# Schematic.net
KiCad netlist of a schematic drawn in Altium Designer
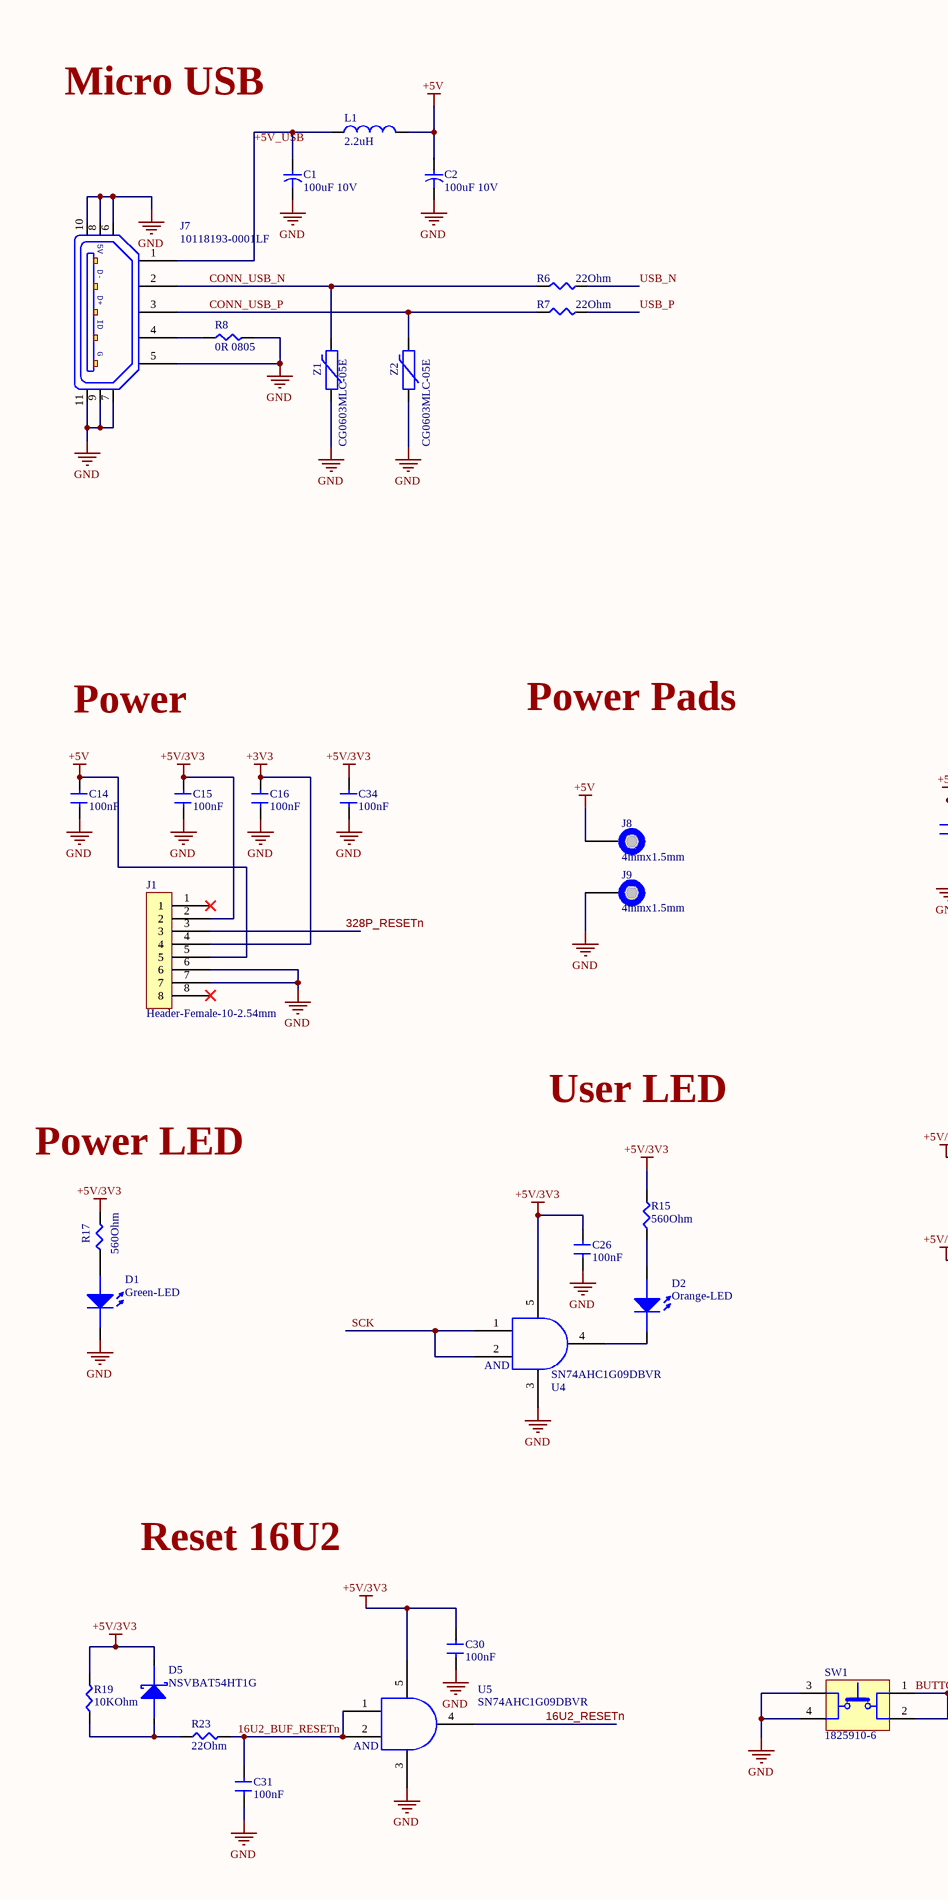
[diagram p0: Schematic.SchDoc, left]
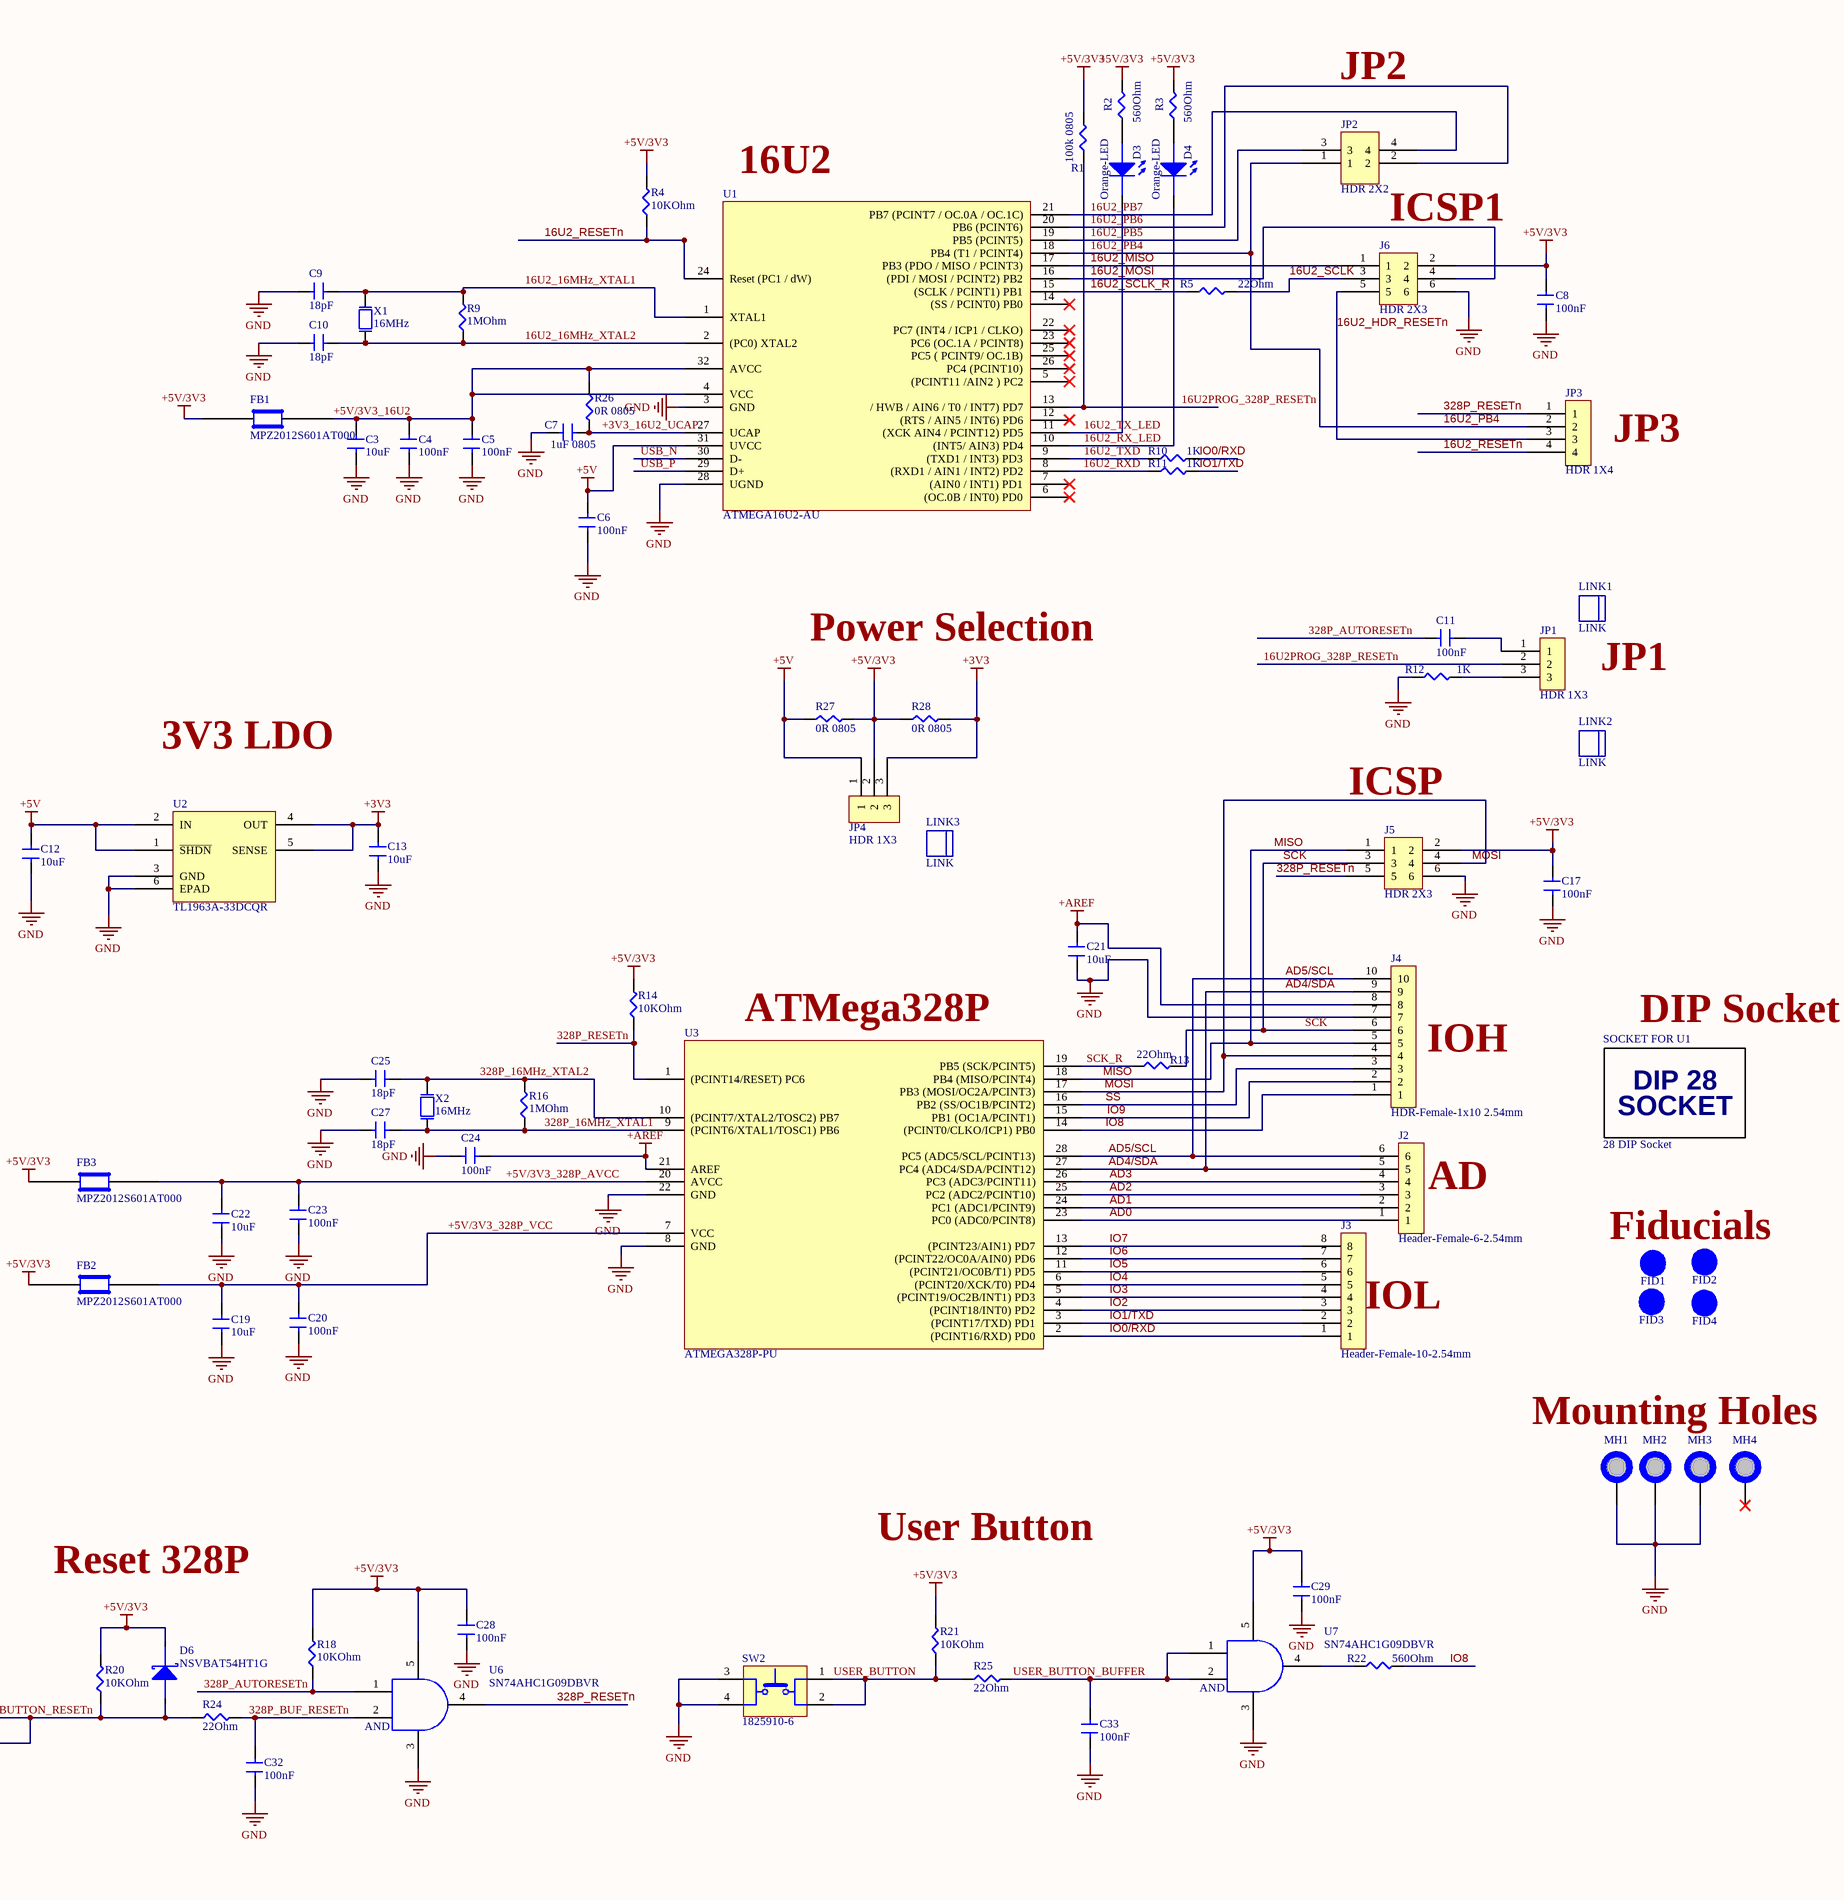
[diagram p1: Schematic.SchDoc, right]

(export (version "E")
  (design (tool "Eeschema 10.0.6"))
  (components
    (comp (ref "C1")
      (value "100uF 10V")
      (footprint "C_ALU_C_SIZE")
      (description "Cap Aluminum 100uF 10V 20% (5 X 5.4mm) SMD 50mA 1000 hr 85°C T/R")
      (fields
        (field (name "MANUFACTURER") "Panasonic")
        (field (name "MANUFACTURER PART NUMBER") "EEE-1AA101WR")
      )
      (libsource (lib "Schematic_Library") (part "100uF 10V"))
    )
    (comp (ref "C2")
      (value "100uF 10V")
      (footprint "C_ALU_C_SIZE")
      (description "Cap Aluminum 100uF 10V 20% (5 X 5.4mm) SMD 50mA 1000 hr 85°C T/R")
      (fields
        (field (name "MANUFACTURER") "Panasonic")
        (field (name "MANUFACTURER PART NUMBER") "EEE-1AA101WR")
      )
      (libsource (lib "Schematic_Library") (part "100uF 10V"))
    )
    (comp (ref "C3")
      (value "10uF")
      (footprint "C-0805-50V")
      (description "Ceramic capacitor SMD 0805 10 µF 16 V 10 %")
      (fields
        (field (name "MANUFACTURER") "Samsung")
        (field (name "MANUFACTURER PART NUMBER") "CL21A106KOQNNNG")
      )
      (libsource (lib "Schematic_Library") (part "10uF"))
    )
    (comp (ref "C4")
      (value "100nF")
      (footprint "C-0805-16V")
      (fields
        (field (name "MANUFACTURER") "Samsung")
        (field (name "MANUFACTURER PART NUMBER") "CL21B104KBCNNNC")
        (field (name "TOLERANCE") "10%")
      )
      (libsource (lib "Schematic_Library") (part "100nF"))
    )
    (comp (ref "C5")
      (value "100nF")
      (footprint "C-0805-16V")
      (fields
        (field (name "MANUFACTURER") "Samsung")
        (field (name "MANUFACTURER PART NUMBER") "CL21B104KBCNNNC")
        (field (name "TOLERANCE") "10%")
      )
      (libsource (lib "Schematic_Library") (part "100nF"))
    )
    (comp (ref "C6")
      (value "100nF")
      (footprint "C-0805-16V")
      (fields
        (field (name "MANUFACTURER") "Samsung")
        (field (name "MANUFACTURER PART NUMBER") "CL21B104KBCNNNC")
        (field (name "TOLERANCE") "10%")
      )
      (libsource (lib "Schematic_Library") (part "100nF"))
    )
    (comp (ref "C7")
      (value "1uF 0805")
      (footprint "C-0805-16V")
      (fields
        (field (name "MANUFACTURER") "TDK")
        (field (name "MANUFACTURER PART NUMBER") "C2012X5R1E105K125AA")
        (field (name "VOLTAGE") "25V")
      )
      (libsource (lib "Schematic_Library") (part "1uF 0805"))
    )
    (comp (ref "C8")
      (value "100nF")
      (footprint "C-0805-16V")
      (fields
        (field (name "MANUFACTURER") "Samsung")
        (field (name "MANUFACTURER PART NUMBER") "CL21B104KBCNNNC")
        (field (name "TOLERANCE") "10%")
      )
      (libsource (lib "Schematic_Library") (part "100nF"))
    )
    (comp (ref "C9")
      (value "18pF")
      (footprint "C-0805-16V")
      (fields
        (field (name "MANUFACTURER") "KEMET")
        (field (name "MANUFACTURER PART NUMBER") "C0805C180K5GACTU")
        (field (name "TOLERANCE") "10%")
      )
      (libsource (lib "Schematic_Library") (part "18pF"))
    )
    (comp (ref "C10")
      (value "18pF")
      (footprint "C-0805-16V")
      (fields
        (field (name "MANUFACTURER") "KEMET")
        (field (name "MANUFACTURER PART NUMBER") "C0805C180K5GACTU")
        (field (name "TOLERANCE") "10%")
      )
      (libsource (lib "Schematic_Library") (part "18pF"))
    )
    (comp (ref "C11")
      (value "100nF")
      (footprint "C-0805-16V")
      (fields
        (field (name "MANUFACTURER") "Samsung")
        (field (name "MANUFACTURER PART NUMBER") "CL21B104KBCNNNC")
        (field (name "TOLERANCE") "10%")
      )
      (libsource (lib "Schematic_Library") (part "100nF"))
    )
    (comp (ref "C12")
      (value "10uF")
      (footprint "C-0805-50V")
      (description "Ceramic capacitor SMD 0805 10 µF 16 V 10 %")
      (fields
        (field (name "MANUFACTURER") "Samsung")
        (field (name "MANUFACTURER PART NUMBER") "CL21A106KOQNNNG")
      )
      (libsource (lib "Schematic_Library") (part "10uF"))
    )
    (comp (ref "C13")
      (value "10uF")
      (footprint "C-0805-50V")
      (description "Ceramic capacitor SMD 0805 10 µF 16 V 10 %")
      (fields
        (field (name "MANUFACTURER") "Samsung")
        (field (name "MANUFACTURER PART NUMBER") "CL21A106KOQNNNG")
      )
      (libsource (lib "Schematic_Library") (part "10uF"))
    )
    (comp (ref "C14")
      (value "100nF")
      (footprint "C-0805-16V")
      (fields
        (field (name "MANUFACTURER") "Samsung")
        (field (name "MANUFACTURER PART NUMBER") "CL21B104KBCNNNC")
        (field (name "TOLERANCE") "10%")
      )
      (libsource (lib "Schematic_Library") (part "100nF"))
    )
    (comp (ref "C15")
      (value "100nF")
      (footprint "C-0805-16V")
      (fields
        (field (name "MANUFACTURER") "Samsung")
        (field (name "MANUFACTURER PART NUMBER") "CL21B104KBCNNNC")
        (field (name "TOLERANCE") "10%")
      )
      (libsource (lib "Schematic_Library") (part "100nF"))
    )
    (comp (ref "C16")
      (value "100nF")
      (footprint "C-0805-16V")
      (fields
        (field (name "MANUFACTURER") "Samsung")
        (field (name "MANUFACTURER PART NUMBER") "CL21B104KBCNNNC")
        (field (name "TOLERANCE") "10%")
      )
      (libsource (lib "Schematic_Library") (part "100nF"))
    )
    (comp (ref "C17")
      (value "100nF")
      (footprint "C-0805-16V")
      (fields
        (field (name "MANUFACTURER") "Samsung")
        (field (name "MANUFACTURER PART NUMBER") "CL21B104KBCNNNC")
        (field (name "TOLERANCE") "10%")
      )
      (libsource (lib "Schematic_Library") (part "100nF"))
    )
    (comp (ref "C19")
      (value "10uF")
      (footprint "C-0805-50V")
      (description "Ceramic capacitor SMD 0805 10 µF 16 V 10 %")
      (fields
        (field (name "MANUFACTURER") "Samsung")
        (field (name "MANUFACTURER PART NUMBER") "CL21A106KOQNNNG")
      )
      (libsource (lib "Schematic_Library") (part "10uF"))
    )
    (comp (ref "C20")
      (value "100nF")
      (footprint "C-0805-16V")
      (fields
        (field (name "MANUFACTURER") "Samsung")
        (field (name "MANUFACTURER PART NUMBER") "CL21B104KBCNNNC")
        (field (name "TOLERANCE") "10%")
      )
      (libsource (lib "Schematic_Library") (part "100nF"))
    )
    (comp (ref "C21")
      (value "10uF")
      (footprint "C-0805-50V")
      (description "Ceramic capacitor SMD 0805 10 µF 16 V 10 %")
      (fields
        (field (name "MANUFACTURER") "Samsung")
        (field (name "MANUFACTURER PART NUMBER") "CL21A106KOQNNNG")
      )
      (libsource (lib "Schematic_Library") (part "10uF"))
    )
    (comp (ref "C22")
      (value "10uF")
      (footprint "C-0805-50V")
      (description "Ceramic capacitor SMD 0805 10 µF 16 V 10 %")
      (fields
        (field (name "MANUFACTURER") "Samsung")
        (field (name "MANUFACTURER PART NUMBER") "CL21A106KOQNNNG")
      )
      (libsource (lib "Schematic_Library") (part "10uF"))
    )
    (comp (ref "C23")
      (value "100nF")
      (footprint "C-0805-16V")
      (fields
        (field (name "MANUFACTURER") "Samsung")
        (field (name "MANUFACTURER PART NUMBER") "CL21B104KBCNNNC")
        (field (name "TOLERANCE") "10%")
      )
      (libsource (lib "Schematic_Library") (part "100nF"))
    )
    (comp (ref "C24")
      (value "100nF")
      (footprint "C-0805-16V")
      (fields
        (field (name "MANUFACTURER") "Samsung")
        (field (name "MANUFACTURER PART NUMBER") "CL21B104KBCNNNC")
        (field (name "TOLERANCE") "10%")
      )
      (libsource (lib "Schematic_Library") (part "100nF"))
    )
    (comp (ref "C25")
      (value "18pF")
      (footprint "C-0805-16V")
      (fields
        (field (name "MANUFACTURER") "KEMET")
        (field (name "MANUFACTURER PART NUMBER") "C0805C180K5GACTU")
        (field (name "TOLERANCE") "10%")
      )
      (libsource (lib "Schematic_Library") (part "18pF"))
    )
    (comp (ref "C26")
      (value "100nF")
      (footprint "C-0805-16V")
      (fields
        (field (name "MANUFACTURER") "Samsung")
        (field (name "MANUFACTURER PART NUMBER") "CL21B104KBCNNNC")
        (field (name "TOLERANCE") "10%")
      )
      (libsource (lib "Schematic_Library") (part "100nF"))
    )
    (comp (ref "C27")
      (value "18pF")
      (footprint "C-0805-16V")
      (fields
        (field (name "MANUFACTURER") "KEMET")
        (field (name "MANUFACTURER PART NUMBER") "C0805C180K5GACTU")
        (field (name "TOLERANCE") "10%")
      )
      (libsource (lib "Schematic_Library") (part "18pF"))
    )
    (comp (ref "C28")
      (value "100nF")
      (footprint "C-0805-16V")
      (fields
        (field (name "MANUFACTURER") "Samsung")
        (field (name "MANUFACTURER PART NUMBER") "CL21B104KBCNNNC")
        (field (name "TOLERANCE") "10%")
      )
      (libsource (lib "Schematic_Library") (part "100nF"))
    )
    (comp (ref "C29")
      (value "100nF")
      (footprint "C-0805-16V")
      (fields
        (field (name "MANUFACTURER") "Samsung")
        (field (name "MANUFACTURER PART NUMBER") "CL21B104KBCNNNC")
        (field (name "TOLERANCE") "10%")
      )
      (libsource (lib "Schematic_Library") (part "100nF"))
    )
    (comp (ref "C30")
      (value "100nF")
      (footprint "C-0805-16V")
      (fields
        (field (name "MANUFACTURER") "Samsung")
        (field (name "MANUFACTURER PART NUMBER") "CL21B104KBCNNNC")
        (field (name "TOLERANCE") "10%")
      )
      (libsource (lib "Schematic_Library") (part "100nF"))
    )
    (comp (ref "C31")
      (value "100nF")
      (footprint "C-0805-16V")
      (fields
        (field (name "MANUFACTURER") "Samsung")
        (field (name "MANUFACTURER PART NUMBER") "CL21B104KBCNNNC")
        (field (name "TOLERANCE") "10%")
      )
      (libsource (lib "Schematic_Library") (part "100nF"))
    )
    (comp (ref "C32")
      (value "100nF")
      (footprint "C-0805-16V")
      (fields
        (field (name "MANUFACTURER") "Samsung")
        (field (name "MANUFACTURER PART NUMBER") "CL21B104KBCNNNC")
        (field (name "TOLERANCE") "10%")
      )
      (libsource (lib "Schematic_Library") (part "100nF"))
    )
    (comp (ref "C33")
      (value "100nF")
      (footprint "C-0805-16V")
      (fields
        (field (name "MANUFACTURER") "Samsung")
        (field (name "MANUFACTURER PART NUMBER") "CL21B104KBCNNNC")
        (field (name "TOLERANCE") "10%")
      )
      (libsource (lib "Schematic_Library") (part "100nF"))
    )
    (comp (ref "C34")
      (value "100nF")
      (footprint "C-0805-16V")
      (fields
        (field (name "MANUFACTURER") "Samsung")
        (field (name "MANUFACTURER PART NUMBER") "CL21B104KBCNNNC")
        (field (name "TOLERANCE") "10%")
      )
      (libsource (lib "Schematic_Library") (part "100nF"))
    )
    (comp (ref "D1")
      (value "Green-LED")
      (footprint "LED-0603")
      (description "LED Uni-Color Green 572nm Automotive 2-Pin Chip 0603(1608Metric) T/R")
      (fields
        (field (name "MANUFACTURER") "Osram Opto")
        (field (name "MANUFACTURER PART NUMBER") "LGL29K-F2J1-24-Z")
      )
      (libsource (lib "Schematic_Library") (part "Green-LED"))
    )
    (comp (ref "D2")
      (value "Orange-LED")
      (footprint "LED-0603")
      (description "OSRAM - LO L29K-H2K1-24-Z - SMARTLED 0603 ORANGE")
      (fields
        (field (name "MANUFACTURER") "Osram Opto")
        (field (name "MANUFACTURER PART NUMBER") "LOL29K-H2K1-24-Z")
      )
      (libsource (lib "Schematic_Library") (part "Orange-LED"))
    )
    (comp (ref "D3")
      (value "Orange-LED")
      (footprint "LED-0603")
      (description "OSRAM - LO L29K-H2K1-24-Z - SMARTLED 0603 ORANGE")
      (fields
        (field (name "MANUFACTURER") "Osram Opto")
        (field (name "MANUFACTURER PART NUMBER") "LOL29K-H2K1-24-Z")
      )
      (libsource (lib "Schematic_Library") (part "Orange-LED"))
    )
    (comp (ref "D4")
      (value "Orange-LED")
      (footprint "LED-0603")
      (description "OSRAM - LO L29K-H2K1-24-Z - SMARTLED 0603 ORANGE")
      (fields
        (field (name "MANUFACTURER") "Osram Opto")
        (field (name "MANUFACTURER PART NUMBER") "LOL29K-H2K1-24-Z")
      )
      (libsource (lib "Schematic_Library") (part "Orange-LED"))
    )
    (comp (ref "D5")
      (value "NSVBAT54HT1G")
      (footprint "SOD323")
      (description "Schottky Diodes & Rectifiers SS SCHOTTKY DIODE")
      (fields (field (name "MANUFACTURER") "ON Semiconductor"))
      (libsource (lib "Schematic_Library") (part "NSVBAT54HT1G"))
    )
    (comp (ref "D6")
      (value "NSVBAT54HT1G")
      (footprint "SOD323")
      (description "Schottky Diodes & Rectifiers SS SCHOTTKY DIODE")
      (fields (field (name "MANUFACTURER") "ON Semiconductor"))
      (libsource (lib "Schematic_Library") (part "NSVBAT54HT1G"))
    )
    (comp (ref "FB1")
      (value "MPZ2012S601AT000")
      (footprint "C-0805-16V")
      (description "FERRITE BEAD 600 OHM 0805 1LN")
      (fields (field (name "MANUFACTURER") "TDK"))
      (libsource (lib "Schematic_Library") (part "MPZ2012S601AT000"))
    )
    (comp (ref "FB2")
      (value "MPZ2012S601AT000")
      (footprint "C-0805-16V")
      (description "FERRITE BEAD 600 OHM 0805 1LN")
      (fields (field (name "MANUFACTURER") "TDK"))
      (libsource (lib "Schematic_Library") (part "MPZ2012S601AT000"))
    )
    (comp (ref "FB3")
      (value "MPZ2012S601AT000")
      (footprint "C-0805-16V")
      (description "FERRITE BEAD 600 OHM 0805 1LN")
      (fields (field (name "MANUFACTURER") "TDK"))
      (libsource (lib "Schematic_Library") (part "MPZ2012S601AT000"))
    )
    (comp (ref "FID1")
      (value "FID_1mm")
      (footprint "FID_40x120")
      (libsource (lib "Schematic_Library") (part "FID_1mm"))
    )
    (comp (ref "FID2")
      (value "FID_1mm")
      (footprint "FID_40x120")
      (libsource (lib "Schematic_Library") (part "FID_1mm"))
    )
    (comp (ref "FID3")
      (value "FID_1mm")
      (footprint "FID_40x120")
      (libsource (lib "Schematic_Library") (part "FID_1mm"))
    )
    (comp (ref "FID4")
      (value "FID_1mm")
      (footprint "FID_40x120")
      (libsource (lib "Schematic_Library") (part "FID_1mm"))
    )
    (comp (ref "J1")
      (value "Header-Female-10-2.54mm")
      (footprint "Header-Female-2.54mm-8")
      (description "CONN HDR 8POS 0.1 TIN PCB")
      (fields
        (field (name "MANUFACTURER") "Sullins")
        (field (name "MANUFACTURER PART NUMBER") "PPTC081LFBN-RC")
      )
      (libsource (lib "") (part "Header-Female-8-2.54mm_1"))
    )
    (comp (ref "J2")
      (value "Header-Female-6-2.54mm")
      (footprint "Header-Female-2.54mm-6")
      (description "Female, 6 C, Straight, .100\"CC; 3.20mm Tail, No Mt. 100u\" Tin; PBT, Phos Bronze, 105 C")
      (fields
        (field (name "MANUFACTURER") "Sullins")
        (field (name "MANUFACTURER PART NUMBER") "PPTC061LFBN-RC")
      )
      (libsource (lib "Schematic_Library") (part "Header-Female-6-2.54mm"))
    )
    (comp (ref "J3")
      (value "Header-Female-10-2.54mm")
      (footprint "Header-Female-2.54mm-8")
      (description "CONN HDR 8POS 0.1 TIN PCB")
      (fields
        (field (name "MANUFACTURER") "Sullins")
        (field (name "MANUFACTURER PART NUMBER") "PPTC081LFBN-RC")
      )
      (libsource (lib "Schematic_Library") (part "Header-Female-8-2.54mm"))
    )
    (comp (ref "J4")
      (value "HDR-Female-1x10 2.54mm")
      (footprint "Header-Female-2.54mm-1x10")
      (description "CONN HDR 10POS 0.079 GOLD PCB")
      (fields
        (field (name "MANUFACTURER") "Sullins")
        (field (name "MANUFACTURER PART NUMBER") "NPPN101BFCN-RC")
      )
      (libsource (lib "Schematic_Library") (part "Header-Female-2.54mm-10"))
    )
    (comp (ref "J5")
      (value "HDR 2X3")
      (footprint "HDR 2x3")
      (fields
        (field (name "MANUFACTURER") "TE Connectivity")
        (field (name "MANUFACTURER PART NUMBER") "87227-3")
      )
      (libsource (lib "Schematic_Library") (part "HDR 2X3"))
    )
    (comp (ref "J6")
      (value "HDR 2X3")
      (footprint "HDR 2x3")
      (fields
        (field (name "MANUFACTURER") "TE Connectivity")
        (field (name "MANUFACTURER PART NUMBER") "87227-3")
      )
      (libsource (lib "Schematic_Library") (part "HDR 2X3"))
    )
    (comp (ref "J7")
      (value "10118193-0001LF")
      (footprint "10118193")
      (description "CONN USB MICRO B RECPT SMT R/A")
      (fields (field (name "MANUFACTURER") "Amphenol FCI"))
      (libsource (lib "Schematic_Library") (part "10118193-0001LF"))
    )
    (comp (ref "J8")
      (value "4mmx1.5mm")
      (footprint "PAD_WITH_HOLE_4mmx1.5mm")
      (libsource (lib "Schematic_Library") (part "PAD_WITH_HOLE_4mmx1.5mm"))
    )
    (comp (ref "J9")
      (value "4mmx1.5mm")
      (footprint "PAD_WITH_HOLE_4mmx1.5mm")
      (libsource (lib "Schematic_Library") (part "PAD_WITH_HOLE_4mmx1.5mm"))
    )
    (comp (ref "JP1")
      (value "HDR 1X3")
      (footprint "Header-1x3")
      (description "BERGSTIK II .100\" SR STRAIGHT")
      (fields
        (field (name "MANUFACTURER") "Amphenol FCI")
        (field (name "MANUFACTURER PART NUMBER") "68001-403HLF")
      )
      (libsource (lib "") (part "HDR 1X3_1"))
    )
    (comp (ref "JP2")
      (value "HDR 2X2")
      (footprint "HDR 2x2")
      (description "67996-404HLF-BERG II 100CC DR ST ;ROHS COMPLIANT: YES")
      (fields
        (field (name "MANUFACTURER") "Amphenol FCI")
        (field (name "MANUFACTURER PART NUMBER") "67996-404HLF")
      )
      (libsource (lib "Schematic_Library") (part "HDR 2X2"))
    )
    (comp (ref "JP3")
      (value "HDR 1X4")
      (footprint "HDR 1x4")
      (description "CONN HEADER VERT 4POS 2.54MM")
      (fields
        (field (name "MANUFACTURER") "Amphenol FCI")
        (field (name "MANUFACTURER PART NUMBER") "68000-204HLF")
      )
      (libsource (lib "Schematic_Library") (part "HDR 1X4"))
    )
    (comp (ref "JP4")
      (value "HDR 1X3")
      (footprint "Header-1x3")
      (description "BERGSTIK II .100\" SR STRAIGHT")
      (fields
        (field (name "MANUFACTURER") "Amphenol FCI")
        (field (name "MANUFACTURER PART NUMBER") "68001-403HLF")
      )
      (libsource (lib "Schematic_Library") (part "HDR 1X3"))
    )
    (comp (ref "L1")
      (value "2.2uH")
      (footprint "C1210 - IND")
      (description "FIXED IND 2.2UH 2A 80 MOHM SMD")
      (fields
        (field (name "MANUFACTURER") "KEMET")
        (field (name "MANUFACTURER PART NUMBER") "L1210R2R2MDWIT")
      )
      (libsource (lib "Schematic_Library") (part "2.2uH"))
    )
    (comp (ref "LINK1")
      (value "LINK")
      (description "CONN JUMPER SHORTING .100\" GOLD")
      (fields
        (field (name "MANUFACTURER") "Sullins")
        (field (name "MANUFACTURER PART NUMBER") "QPC02SXGN-RC")
      )
      (libsource (lib "Schematic_Library") (part "LINK"))
    )
    (comp (ref "LINK2")
      (value "LINK")
      (description "CONN JUMPER SHORTING .100\" GOLD")
      (fields
        (field (name "MANUFACTURER") "Sullins")
        (field (name "MANUFACTURER PART NUMBER") "QPC02SXGN-RC")
      )
      (libsource (lib "Schematic_Library") (part "LINK"))
    )
    (comp (ref "LINK3")
      (value "LINK")
      (description "CONN JUMPER SHORTING .100\" GOLD")
      (fields
        (field (name "MANUFACTURER") "Sullins")
        (field (name "MANUFACTURER PART NUMBER") "QPC02SXGN-RC")
      )
      (libsource (lib "Schematic_Library") (part "LINK"))
    )
    (comp (ref "MH1")
      (value "MH_7.4mm_3.2mm")
      (footprint "MH_7.44mm_3.2mm")
      (libsource (lib "Schematic_Library") (part "MH_7.4mm_3.2mm"))
    )
    (comp (ref "MH2")
      (value "MH_7.4mm_3.2mm")
      (footprint "MH_7.44mm_3.2mm")
      (libsource (lib "Schematic_Library") (part "MH_7.4mm_3.2mm"))
    )
    (comp (ref "MH3")
      (value "MH_7.4mm_3.2mm")
      (footprint "MH_7.44mm_3.2mm")
      (libsource (lib "Schematic_Library") (part "MH_7.4mm_3.2mm"))
    )
    (comp (ref "MH4")
      (value "MH_7.4mm_3.2mm_Non Plated")
      (footprint "MH_7.4mm_3.2mm_Non_Plated")
      (libsource (lib "Schematic_Library") (part "MH_7.4mm_3.2mm_Non Plated"))
    )
    (comp (ref "R1")
      (value "100k 0805")
      (footprint "R-0805")
      (description "YAGEO         RC0805FR-07100KL            RES, THICK FILM, 100K, 1%, 0.125W, 0805, REEL")
      (fields
        (field (name "MANUFACTURER") "Yageo")
        (field (name "MANUFACTURER PART NUMBER") "RC0805FR-07100KL")
      )
      (libsource (lib "Schematic_Library") (part "100k 0805"))
    )
    (comp (ref "R2")
      (value "560Ohm")
      (footprint "R-0805")
      (description "RES SMD 560 OHM 1% 1/8W 0805")
      (fields
        (field (name "MANUFACTURER") "Yageo")
        (field (name "MANUFACTURER PART NUMBER") "RT0805FRE07560RL")
      )
      (libsource (lib "Schematic_Library") (part "560Ohm"))
    )
    (comp (ref "R3")
      (value "560Ohm")
      (footprint "R-0805")
      (description "RES SMD 560 OHM 1% 1/8W 0805")
      (fields
        (field (name "MANUFACTURER") "Yageo")
        (field (name "MANUFACTURER PART NUMBER") "RT0805FRE07560RL")
      )
      (libsource (lib "Schematic_Library") (part "560Ohm"))
    )
    (comp (ref "R4")
      (value "10KOhm")
      (footprint "R-0805")
      (description "RES SMD 10K OHM 1% 1/8W 0805")
      (fields
        (field (name "MANUFACTURER") "Yageo")
        (field (name "MANUFACTURER PART NUMBER") "AC0805FR-0710KL")
      )
      (libsource (lib "Schematic_Library") (part "10KOhm"))
    )
    (comp (ref "R5")
      (value "22Ohm")
      (footprint "R-0805")
      (description "YAGEO         RC0805FR-072R2L             RES, THICK FILM, 2R2, 1%, 0.125W, 0805")
      (fields
        (field (name "MANUFACTURER") "Yageo")
        (field (name "MANUFACTURER PART NUMBER") "RC0805FR-072R2L")
      )
      (libsource (lib "Schematic_Library") (part "22Ohm"))
    )
    (comp (ref "R6")
      (value "22Ohm")
      (footprint "R-0805")
      (description "YAGEO         RC0805FR-072R2L             RES, THICK FILM, 2R2, 1%, 0.125W, 0805")
      (fields
        (field (name "MANUFACTURER") "Yageo")
        (field (name "MANUFACTURER PART NUMBER") "RC0805FR-072R2L")
      )
      (libsource (lib "Schematic_Library") (part "22Ohm"))
    )
    (comp (ref "R7")
      (value "22Ohm")
      (footprint "R-0805")
      (description "YAGEO         RC0805FR-072R2L             RES, THICK FILM, 2R2, 1%, 0.125W, 0805")
      (fields
        (field (name "MANUFACTURER") "Yageo")
        (field (name "MANUFACTURER PART NUMBER") "RC0805FR-072R2L")
      )
      (libsource (lib "Schematic_Library") (part "22Ohm"))
    )
    (comp (ref "R8")
      (value "0R 0805")
      (footprint "R-0805")
      (description "Surface Mount Thick Film Resistor, RC Series, 125 mW, - 5%, 150 V, 0805 [2012 Metric]")
      (fields
        (field (name "MANUFACTURER") "Yageo")
        (field (name "MANUFACTURER PART NUMBER") "RC0805JR-070RL")
      )
      (libsource (lib "Schematic_Library") (part "0R 0805"))
    )
    (comp (ref "R9")
      (value "1MOhm")
      (footprint "R-0805")
      (description "Resistor; Thick Film; Res 1 Megohms; Pwr-Rtg 0.125 W; Tol 1%; SMT; 0805")
      (fields
        (field (name "MANUFACTURER") "TE Connectivity")
        (field (name "MANUFACTURER PART NUMBER") "CRG0805F1M0")
      )
      (libsource (lib "Schematic_Library") (part "1MOhm"))
    )
    (comp (ref "R10")
      (value "1K")
      (footprint "R-0805")
      (fields
        (field (name "MANUFACTURER") "Yageo")
        (field (name "MANUFACTURER PART NUMBER") "RC0805FR-071KL")
        (field (name "TOLERANCE") "1%")
      )
      (libsource (lib "Schematic_Library") (part "1KOhm"))
    )
    (comp (ref "R11")
      (value "1K")
      (footprint "R-0805")
      (fields
        (field (name "MANUFACTURER") "Yageo")
        (field (name "MANUFACTURER PART NUMBER") "RC0805FR-071KL")
        (field (name "TOLERANCE") "1%")
      )
      (libsource (lib "Schematic_Library") (part "1KOhm"))
    )
    (comp (ref "R12")
      (value "1K")
      (footprint "R-0805")
      (fields
        (field (name "MANUFACTURER") "Yageo")
        (field (name "MANUFACTURER PART NUMBER") "RC0805FR-071KL")
        (field (name "TOLERANCE") "1%")
      )
      (libsource (lib "Schematic_Library") (part "1KOhm"))
    )
    (comp (ref "R13")
      (value "22Ohm")
      (footprint "R-0805")
      (description "YAGEO         RC0805FR-072R2L             RES, THICK FILM, 2R2, 1%, 0.125W, 0805")
      (fields
        (field (name "MANUFACTURER") "Yageo")
        (field (name "MANUFACTURER PART NUMBER") "RC0805FR-072R2L")
      )
      (libsource (lib "Schematic_Library") (part "22Ohm"))
    )
    (comp (ref "R14")
      (value "10KOhm")
      (footprint "R-0805")
      (description "RES SMD 10K OHM 1% 1/8W 0805")
      (fields
        (field (name "MANUFACTURER") "Yageo")
        (field (name "MANUFACTURER PART NUMBER") "AC0805FR-0710KL")
      )
      (libsource (lib "Schematic_Library") (part "10KOhm"))
    )
    (comp (ref "R15")
      (value "560Ohm")
      (footprint "R-0805")
      (description "RES SMD 560 OHM 1% 1/8W 0805")
      (fields
        (field (name "MANUFACTURER") "Yageo")
        (field (name "MANUFACTURER PART NUMBER") "RT0805FRE07560RL")
      )
      (libsource (lib "Schematic_Library") (part "560Ohm"))
    )
    (comp (ref "R16")
      (value "1MOhm")
      (footprint "R-0805")
      (description "Resistor; Thick Film; Res 1 Megohms; Pwr-Rtg 0.125 W; Tol 1%; SMT; 0805")
      (fields
        (field (name "MANUFACTURER") "TE Connectivity")
        (field (name "MANUFACTURER PART NUMBER") "CRG0805F1M0")
      )
      (libsource (lib "Schematic_Library") (part "1MOhm"))
    )
    (comp (ref "R17")
      (value "560Ohm")
      (footprint "R-0805")
      (description "RES SMD 560 OHM 1% 1/8W 0805")
      (fields
        (field (name "MANUFACTURER") "Yageo")
        (field (name "MANUFACTURER PART NUMBER") "RT0805FRE07560RL")
      )
      (libsource (lib "Schematic_Library") (part "560Ohm"))
    )
    (comp (ref "R18")
      (value "10KOhm")
      (footprint "R-0805")
      (description "RES SMD 10K OHM 1% 1/8W 0805")
      (fields
        (field (name "MANUFACTURER") "Yageo")
        (field (name "MANUFACTURER PART NUMBER") "AC0805FR-0710KL")
      )
      (libsource (lib "Schematic_Library") (part "10KOhm"))
    )
    (comp (ref "R19")
      (value "10KOhm")
      (footprint "R-0805")
      (description "RES SMD 10K OHM 1% 1/8W 0805")
      (fields
        (field (name "MANUFACTURER") "Yageo")
        (field (name "MANUFACTURER PART NUMBER") "AC0805FR-0710KL")
      )
      (libsource (lib "Schematic_Library") (part "10KOhm"))
    )
    (comp (ref "R20")
      (value "10KOhm")
      (footprint "R-0805")
      (description "RES SMD 10K OHM 1% 1/8W 0805")
      (fields
        (field (name "MANUFACTURER") "Yageo")
        (field (name "MANUFACTURER PART NUMBER") "AC0805FR-0710KL")
      )
      (libsource (lib "Schematic_Library") (part "10KOhm"))
    )
    (comp (ref "R21")
      (value "10KOhm")
      (footprint "R-0805")
      (description "RES SMD 10K OHM 1% 1/8W 0805")
      (fields
        (field (name "MANUFACTURER") "Yageo")
        (field (name "MANUFACTURER PART NUMBER") "AC0805FR-0710KL")
      )
      (libsource (lib "Schematic_Library") (part "10KOhm"))
    )
    (comp (ref "R22")
      (value "560Ohm")
      (footprint "R-0805")
      (description "RES SMD 560 OHM 1% 1/8W 0805")
      (fields
        (field (name "MANUFACTURER") "Yageo")
        (field (name "MANUFACTURER PART NUMBER") "RT0805FRE07560RL")
      )
      (libsource (lib "Schematic_Library") (part "560Ohm"))
    )
    (comp (ref "R23")
      (value "22Ohm")
      (footprint "R-0805")
      (description "YAGEO         RC0805FR-072R2L             RES, THICK FILM, 2R2, 1%, 0.125W, 0805")
      (fields
        (field (name "MANUFACTURER") "Yageo")
        (field (name "MANUFACTURER PART NUMBER") "RC0805FR-072R2L")
      )
      (libsource (lib "Schematic_Library") (part "22Ohm"))
    )
    (comp (ref "R24")
      (value "22Ohm")
      (footprint "R-0805")
      (description "YAGEO         RC0805FR-072R2L             RES, THICK FILM, 2R2, 1%, 0.125W, 0805")
      (fields
        (field (name "MANUFACTURER") "Yageo")
        (field (name "MANUFACTURER PART NUMBER") "RC0805FR-072R2L")
      )
      (libsource (lib "Schematic_Library") (part "22Ohm"))
    )
    (comp (ref "R25")
      (value "22Ohm")
      (footprint "R-0805")
      (description "YAGEO         RC0805FR-072R2L             RES, THICK FILM, 2R2, 1%, 0.125W, 0805")
      (fields
        (field (name "MANUFACTURER") "Yageo")
        (field (name "MANUFACTURER PART NUMBER") "RC0805FR-072R2L")
      )
      (libsource (lib "Schematic_Library") (part "22Ohm"))
    )
    (comp (ref "R26")
      (value "0R 0805")
      (footprint "R-0805")
      (description "Surface Mount Thick Film Resistor, RC Series, 125 mW, - 5%, 150 V, 0805 [2012 Metric]")
      (fields
        (field (name "MANUFACTURER") "Yageo")
        (field (name "MANUFACTURER PART NUMBER") "RC0805JR-070RL")
      )
      (libsource (lib "Schematic_Library") (part "0R 0805"))
    )
    (comp (ref "R27")
      (value "0R 0805")
      (footprint "R-0805")
      (description "Surface Mount Thick Film Resistor, RC Series, 125 mW, - 5%, 150 V, 0805 [2012 Metric]")
      (fields
        (field (name "MANUFACTURER") "Yageo")
        (field (name "MANUFACTURER PART NUMBER") "RC0805JR-070RL")
      )
      (libsource (lib "Schematic_Library") (part "0R 0805"))
    )
    (comp (ref "R28")
      (value "0R 0805")
      (footprint "R-0805")
      (description "Surface Mount Thick Film Resistor, RC Series, 125 mW, - 5%, 150 V, 0805 [2012 Metric]")
      (fields
        (field (name "MANUFACTURER") "Yageo")
        (field (name "MANUFACTURER PART NUMBER") "RC0805JR-070RL")
      )
      (libsource (lib "Schematic_Library") (part "0R 0805"))
    )
    (comp (ref "SOCKET FOR U1")
      (value "28 DIP Socket")
      (footprint "28-DIP_7.62mm_Socket")
      (description "CONN IC DIP SOCKET 28POS TIN")
      (fields (field (name "MANUFACTURER") "3M") (field (name "MANUFACTURER PART NUMBER") "4828-6000-CP"))
      (libsource (lib "Schematic_Library") (part "28 DIP Socket"))
    )
    (comp (ref "SW1")
      (value "1825910-6")
      (footprint "Switch")
      (description "SWITCH TACTILE SPST-NO 0.05A 24V")
      (fields (field (name "MANUFACTURER") "TE Connectivity Alcoswitch"))
      (libsource (lib "Schematic_Library") (part "1825910-6"))
    )
    (comp (ref "SW2")
      (value "1825910-6")
      (footprint "Switch")
      (description "SWITCH TACTILE SPST-NO 0.05A 24V")
      (fields (field (name "MANUFACTURER") "TE Connectivity Alcoswitch"))
      (libsource (lib "Schematic_Library") (part "1825910-6"))
    )
    (comp (ref "U1")
      (value "ATMEGA16U2-AU")
      (footprint "Quad32")
      (description "MICROCHIP - ATMEGA16U2-AU - MCU, 8BIT, MEGAAVR, 16MHZ, TQFP-32")
      (fields (field (name "MANUFACTURER") "Microchip / Atmel"))
      (libsource (lib "Schematic_Library") (part "ATMEGA16U2-AU"))
    )
    (comp (ref "U2")
      (value "TL1963A-33DCQR")
      (footprint "DCQ-3V3LDO")
      (description "IC REG LINEAR 3.3V 1.5A SOT223-6")
      (fields (field (name "MANUFACTURER") "Texas Instruments"))
      (libsource (lib "Schematic_Library") (part "TL1963A-33DCQR"))
    )
    (comp (ref "U3")
      (value "ATMEGA328P-PU")
      (footprint "DIP28")
      (description "ATMEGA328P-PU; 8 bit Microcontroller AVR 20MHz 1; 32kb Flash; 2kb RAM; I2C SPI 2")
      (fields (field (name "MANUFACTURER") "Microchip / Atmel"))
      (libsource (lib "Schematic_Library") (part "ATMEGA328P-PU"))
    )
    (comp (ref "U4")
      (value "SN74AHC1G09DBVR")
      (footprint "DBV-SOT-23_5")
      (description "TEXAS INSTRUMENTS - SN74AHC1G09DBVR - AND Gate, 74AHC1G09, 2 Input, 2 V to 5.5 V, SOT-23-5")
      (fields (field (name "MANUFACTURER") "Texas Instruments"))
      (libsource (lib "Schematic_Library") (part "SN74AHC1G09DBVR"))
    )
    (comp (ref "U5")
      (value "SN74AHC1G09DBVR")
      (footprint "DBV-SOT-23_5")
      (description "TEXAS INSTRUMENTS - SN74AHC1G09DBVR - AND Gate, 74AHC1G09, 2 Input, 2 V to 5.5 V, SOT-23-5")
      (fields (field (name "MANUFACTURER") "Texas Instruments"))
      (libsource (lib "Schematic_Library") (part "SN74AHC1G09DBVR"))
    )
    (comp (ref "U6")
      (value "SN74AHC1G09DBVR")
      (footprint "DBV-SOT-23_5")
      (description "TEXAS INSTRUMENTS - SN74AHC1G09DBVR - AND Gate, 74AHC1G09, 2 Input, 2 V to 5.5 V, SOT-23-5")
      (fields (field (name "MANUFACTURER") "Texas Instruments"))
      (libsource (lib "Schematic_Library") (part "SN74AHC1G09DBVR"))
    )
    (comp (ref "U7")
      (value "SN74AHC1G09DBVR")
      (footprint "DBV-SOT-23_5")
      (description "TEXAS INSTRUMENTS - SN74AHC1G09DBVR - AND Gate, 74AHC1G09, 2 Input, 2 V to 5.5 V, SOT-23-5")
      (fields (field (name "MANUFACTURER") "Texas Instruments"))
      (libsource (lib "Schematic_Library") (part "SN74AHC1G09DBVR"))
    )
    (comp (ref "X1")
      (value "16MHz")
      (footprint "XTAL-16MHz")
      (description "CRYSTAL 16.0000MHZ 18PF SMD")
      (fields
        (field (name "MANUFACTURER") "Abracon")
        (field (name "MANUFACTURER PART NUMBER") "ABM7-16.000MHZ-D2Y-T")
      )
      (libsource (lib "Schematic_Library") (part "16MHz"))
    )
    (comp (ref "X2")
      (value "16MHz")
      (footprint "XTAL-16MHz")
      (description "CRYSTAL 16.0000MHZ 18PF SMD")
      (fields
        (field (name "MANUFACTURER") "Abracon")
        (field (name "MANUFACTURER PART NUMBER") "ABM7-16.000MHZ-D2Y-T")
      )
      (libsource (lib "Schematic_Library") (part "16MHz"))
    )
    (comp (ref "Z1")
      (value "CG0603MLC-05E")
      (footprint "R0603")
      (description "VARISTOR 0603")
      (fields (field (name "MANUFACTURER") "Bourns") (field (name "VOLTAGE") "5V"))
      (libsource (lib "Schematic_Library") (part "CG0603MLC-05E"))
    )
    (comp (ref "Z2")
      (value "CG0603MLC-05E")
      (footprint "R0603")
      (description "VARISTOR 0603")
      (fields (field (name "MANUFACTURER") "Bourns") (field (name "VOLTAGE") "5V"))
      (libsource (lib "Schematic_Library") (part "CG0603MLC-05E"))
    )
  )
  (nets
    (net (code "1") (name "+3V3") (class "Default")
      (node (ref "C13") (pin "2") (pinfunction "2_2") (pintype "passive"))
      (node (ref "C16") (pin "2") (pinfunction "2_2") (pintype "passive"))
      (node (ref "J1") (pin "4") (pinfunction "4_4") (pintype "passive"))
      (node (ref "JP4") (pin "3") (pinfunction "3_3") (pintype "passive"))
      (node (ref "R28") (pin "2") (pinfunction "2_2") (pintype "passive"))
      (node (ref "U2") (pin "4") (pinfunction "OUT_4") (pintype "passive"))
      (node (ref "U2") (pin "5") (pinfunction "SENSE_5") (pintype "passive"))
    )
    (net (code "2") (name "+5V") (class "Default")
      (node (ref "C12") (pin "2") (pinfunction "2_2") (pintype "passive"))
      (node (ref "C14") (pin "2") (pinfunction "2_2") (pintype "passive"))
      (node (ref "C2") (pin "1") (pinfunction "1_1") (pintype "passive"))
      (node (ref "C6") (pin "2") (pinfunction "2_2") (pintype "passive"))
      (node (ref "J1") (pin "5") (pinfunction "5_5") (pintype "passive"))
      (node (ref "J8") (pin "1") (pinfunction "1_1") (pintype "passive"))
      (node (ref "JP4") (pin "1") (pinfunction "1_1") (pintype "passive"))
      (node (ref "L1") (pin "2") (pinfunction "2_2") (pintype "passive"))
      (node (ref "R27") (pin "1") (pinfunction "1_1") (pintype "passive"))
      (node (ref "U1") (pin "31") (pinfunction "UVCC_31") (pintype "passive"))
      (node (ref "U2") (pin "1") (pinfunction "~{SHDN}_1") (pintype "passive"))
      (node (ref "U2") (pin "2") (pinfunction "IN_2") (pintype "passive"))
    )
    (net (code "3") (name "+5V{slash}3V3") (class "Default")
      (node (ref "C15") (pin "2") (pinfunction "2_2") (pintype "passive"))
      (node (ref "C17") (pin "2") (pinfunction "2_2") (pintype "passive"))
      (node (ref "C26") (pin "2") (pinfunction "2_2") (pintype "passive"))
      (node (ref "C28") (pin "2") (pinfunction "2_2") (pintype "passive"))
      (node (ref "C29") (pin "2") (pinfunction "2_2") (pintype "passive"))
      (node (ref "C30") (pin "2") (pinfunction "2_2") (pintype "passive"))
      (node (ref "C34") (pin "2") (pinfunction "2_2") (pintype "passive"))
      (node (ref "C8") (pin "2") (pinfunction "2_2") (pintype "passive"))
      (node (ref "D5") (pin "1") (pinfunction "Cathode_1") (pintype "passive"))
      (node (ref "D6") (pin "1") (pinfunction "Cathode_1") (pintype "passive"))
      (node (ref "FB1") (pin "1") (pinfunction "1_1") (pintype "passive"))
      (node (ref "FB2") (pin "1") (pinfunction "1_1") (pintype "passive"))
      (node (ref "FB3") (pin "1") (pinfunction "1_1") (pintype "passive"))
      (node (ref "J1") (pin "2") (pinfunction "2_2") (pintype "passive"))
      (node (ref "J5") (pin "2") (pinfunction "2_2") (pintype "passive"))
      (node (ref "J6") (pin "2") (pinfunction "2_2") (pintype "passive"))
      (node (ref "JP4") (pin "2") (pinfunction "2_2") (pintype "passive"))
      (node (ref "R1") (pin "2") (pinfunction "2_2") (pintype "passive"))
      (node (ref "R14") (pin "2") (pinfunction "2_2") (pintype "passive"))
      (node (ref "R15") (pin "2") (pinfunction "2_2") (pintype "passive"))
      (node (ref "R17") (pin "2") (pinfunction "2_2") (pintype "passive"))
      (node (ref "R18") (pin "2") (pinfunction "2_2") (pintype "passive"))
      (node (ref "R19") (pin "2") (pinfunction "2_2") (pintype "passive"))
      (node (ref "R2") (pin "2") (pinfunction "2_2") (pintype "passive"))
      (node (ref "R20") (pin "2") (pinfunction "2_2") (pintype "passive"))
      (node (ref "R21") (pin "2") (pinfunction "2_2") (pintype "passive"))
      (node (ref "R27") (pin "2") (pinfunction "2_2") (pintype "passive"))
      (node (ref "R28") (pin "1") (pinfunction "1_1") (pintype "passive"))
      (node (ref "R3") (pin "2") (pinfunction "2_2") (pintype "passive"))
      (node (ref "R4") (pin "2") (pinfunction "2_2") (pintype "passive"))
      (node (ref "U4") (pin "5") (pinfunction "5_5") (pintype "passive"))
      (node (ref "U5") (pin "5") (pinfunction "5_5") (pintype "passive"))
      (node (ref "U6") (pin "5") (pinfunction "5_5") (pintype "passive"))
      (node (ref "U7") (pin "5") (pinfunction "5_5") (pintype "passive"))
    )
    (net (code "4") (name "+AREF") (class "Default")
      (node (ref "C21") (pin "2") (pinfunction "2_2") (pintype "passive"))
      (node (ref "C24") (pin "2") (pinfunction "2_2") (pintype "passive"))
      (node (ref "J4") (pin "8") (pinfunction "8_8") (pintype "passive"))
      (node (ref "U3") (pin "21") (pinfunction "AREF_21") (pintype "passive"))
    )
    (net (code "5") (name "/+3V3_16U2_UCAP") (class "Default")
      (node (ref "C7") (pin "2") (pinfunction "2_2") (pintype "passive"))
      (node (ref "R26") (pin "2") (pinfunction "2_2") (pintype "passive"))
      (node (ref "U1") (pin "27") (pinfunction "UCAP_27") (pintype "passive"))
    )
    (net (code "6") (name "/+5V_USB") (class "Default")
      (node (ref "C1") (pin "1") (pinfunction "1_1") (pintype "passive"))
      (node (ref "J7") (pin "1") (pinfunction "1_1") (pintype "passive"))
      (node (ref "L1") (pin "1") (pinfunction "1_1") (pintype "passive"))
    )
    (net (code "7") (name "/+5V{slash}3V3_16U2") (class "Default")
      (node (ref "C3") (pin "2") (pinfunction "2_2") (pintype "passive"))
      (node (ref "C4") (pin "2") (pinfunction "2_2") (pintype "passive"))
      (node (ref "C5") (pin "2") (pinfunction "2_2") (pintype "passive"))
      (node (ref "FB1") (pin "2") (pinfunction "2_2") (pintype "passive"))
      (node (ref "R26") (pin "1") (pinfunction "1_1") (pintype "passive"))
      (node (ref "U1") (pin "32") (pinfunction "AVCC_32") (pintype "passive"))
      (node (ref "U1") (pin "4") (pinfunction "VCC_4") (pintype "passive"))
    )
    (net (code "8") (name "/+5V{slash}3V3_328P_AVCC") (class "Default")
      (node (ref "C22") (pin "2") (pinfunction "2_2") (pintype "passive"))
      (node (ref "C23") (pin "2") (pinfunction "2_2") (pintype "passive"))
      (node (ref "FB3") (pin "2") (pinfunction "2_2") (pintype "passive"))
      (node (ref "U3") (pin "20") (pinfunction "AVCC_20") (pintype "passive"))
    )
    (net (code "9") (name "/+5V{slash}3V3_328P_VCC") (class "Default")
      (node (ref "C19") (pin "2") (pinfunction "2_2") (pintype "passive"))
      (node (ref "C20") (pin "2") (pinfunction "2_2") (pintype "passive"))
      (node (ref "FB2") (pin "2") (pinfunction "2_2") (pintype "passive"))
      (node (ref "U3") (pin "7") (pinfunction "VCC_7") (pintype "passive"))
    )
    (net (code "10") (name "/16U2PROG_328P_RESETn") (class "Default")
      (node (ref "JP1") (pin "2") (pinfunction "2_2") (pintype "passive"))
      (node (ref "R1") (pin "1") (pinfunction "1_1") (pintype "passive"))
      (node (ref "U1") (pin "13") (pinfunction "/_HWB_/_AIN6_/_T0_/_INT7)_PD7_13") (pintype "passive"))
    )
    (net (code "11") (name "/16U2_16MHz_XTAL1") (class "Default")
      (node (ref "C9") (pin "2") (pinfunction "2_2") (pintype "passive"))
      (node (ref "R9") (pin "2") (pinfunction "2_2") (pintype "passive"))
      (node (ref "U1") (pin "1") (pinfunction "XTAL1_1") (pintype "passive"))
      (node (ref "X1") (pin "2") (pinfunction "2_2") (pintype "passive"))
    )
    (net (code "12") (name "/16U2_16MHz_XTAL2") (class "Default")
      (node (ref "C10") (pin "2") (pinfunction "2_2") (pintype "passive"))
      (node (ref "R9") (pin "1") (pinfunction "1_1") (pintype "passive"))
      (node (ref "U1") (pin "2") (pinfunction "(PC0)_XTAL2_2") (pintype "passive"))
      (node (ref "X1") (pin "1") (pinfunction "1_1") (pintype "passive"))
    )
    (net (code "13") (name "/16U2_BUF_RESETn") (class "Default")
      (node (ref "C31") (pin "2") (pinfunction "2_2") (pintype "passive"))
      (node (ref "R23") (pin "2") (pinfunction "2_2") (pintype "passive"))
      (node (ref "U5") (pin "1") (pinfunction "1_1") (pintype "passive"))
      (node (ref "U5") (pin "2") (pinfunction "2_2") (pintype "passive"))
    )
    (net (code "14") (name "/16U2_HDR_RESETn") (class "Default")
      (node (ref "J6") (pin "5") (pinfunction "5_5") (pintype "passive"))
      (node (ref "JP3") (pin "3") (pinfunction "3_3") (pintype "passive"))
    )
    (net (code "15") (name "/16U2_MISO") (class "Default")
      (node (ref "J6") (pin "1") (pinfunction "1_1") (pintype "passive"))
      (node (ref "U1") (pin "17") (pinfunction "PB3_(PDO_/_MISO_/_PCINT3)_17") (pintype "passive"))
    )
    (net (code "16") (name "/16U2_MOSI") (class "Default")
      (node (ref "J6") (pin "4") (pinfunction "4_4") (pintype "passive"))
      (node (ref "U1") (pin "16") (pinfunction "(PDI_/_MOSI_/_PCINT2)_PB2_16") (pintype "passive"))
    )
    (net (code "17") (name "/16U2_PB4") (class "Default")
      (node (ref "JP2") (pin "1") (pinfunction "1_1") (pintype "passive"))
      (node (ref "JP3") (pin "2") (pinfunction "2_2") (pintype "passive"))
      (node (ref "U1") (pin "18") (pinfunction "PB4_(T1_/_PCINT4)_18") (pintype "passive"))
    )
    (net (code "18") (name "/16U2_PB5") (class "Default")
      (node (ref "JP2") (pin "3") (pinfunction "3_3") (pintype "passive"))
      (node (ref "U1") (pin "19") (pinfunction "PB5_(PCINT5)_19") (pintype "passive"))
    )
    (net (code "19") (name "/16U2_PB6") (class "Default")
      (node (ref "JP2") (pin "2") (pinfunction "2_2") (pintype "passive"))
      (node (ref "U1") (pin "20") (pinfunction "PB6_(PCINT6)_20") (pintype "passive"))
    )
    (net (code "20") (name "/16U2_PB7") (class "Default")
      (node (ref "JP2") (pin "4") (pinfunction "4_4") (pintype "passive"))
      (node (ref "U1") (pin "21") (pinfunction "PB7_(PCINT7_/_OC.0A_/_OC.1C)_21") (pintype "passive"))
    )
    (net (code "21") (name "/16U2_RESETn") (class "Default")
      (node (ref "JP3") (pin "4") (pinfunction "4_4") (pintype "passive"))
      (node (ref "R4") (pin "1") (pinfunction "1_1") (pintype "passive"))
      (node (ref "U1") (pin "24") (pinfunction "Reset_(PC1_/_dW)_24") (pintype "passive"))
      (node (ref "U5") (pin "4") (pinfunction "4_4") (pintype "passive"))
    )
    (net (code "22") (name "/16U2_RXD") (class "Default")
      (node (ref "R11") (pin "1") (pinfunction "1_1") (pintype "passive"))
      (node (ref "U1") (pin "8") (pinfunction "(RXD1_/_AIN1_/_INT2)_PD2_8") (pintype "passive"))
    )
    (net (code "23") (name "/16U2_RX_LED") (class "Default")
      (node (ref "D4") (pin "1") (pinfunction "1_1") (pintype "passive"))
      (node (ref "U1") (pin "10") (pinfunction "(INT5/_AIN3)_PD4_10") (pintype "passive"))
    )
    (net (code "24") (name "/16U2_SCLK") (class "Default")
      (node (ref "J6") (pin "3") (pinfunction "3_3") (pintype "passive"))
      (node (ref "R5") (pin "2") (pinfunction "2_2") (pintype "passive"))
    )
    (net (code "25") (name "/16U2_SCLK_R") (class "Default")
      (node (ref "R5") (pin "1") (pinfunction "1_1") (pintype "passive"))
      (node (ref "U1") (pin "15") (pinfunction "(SCLK_/_PCINT1)_PB1_15") (pintype "passive"))
    )
    (net (code "26") (name "/16U2_TXD") (class "Default")
      (node (ref "R10") (pin "1") (pinfunction "1_1") (pintype "passive"))
      (node (ref "U1") (pin "9") (pinfunction "(TXD1_/_INT3)_PD3_9") (pintype "passive"))
    )
    (net (code "27") (name "/16U2_TX_LED") (class "Default")
      (node (ref "D3") (pin "1") (pinfunction "1_1") (pintype "passive"))
      (node (ref "U1") (pin "11") (pinfunction "(XCK_AIN4_/_PCINT12)_PD5_11") (pintype "passive"))
    )
    (net (code "28") (name "/328P_16MHz_XTAL1") (class "Default")
      (node (ref "C27") (pin "2") (pinfunction "2_2") (pintype "passive"))
      (node (ref "R16") (pin "1") (pinfunction "1_1") (pintype "passive"))
      (node (ref "U3") (pin "9") (pinfunction "(PCINT6/XTAL1/TOSC1)_PB6_9") (pintype "passive"))
      (node (ref "X2") (pin "1") (pinfunction "1_1") (pintype "passive"))
    )
    (net (code "29") (name "/328P_16MHz_XTAL2") (class "Default")
      (node (ref "C25") (pin "2") (pinfunction "2_2") (pintype "passive"))
      (node (ref "R16") (pin "2") (pinfunction "2_2") (pintype "passive"))
      (node (ref "U3") (pin "10") (pinfunction "(PCINT7/XTAL2/TOSC2)_PB7_10") (pintype "passive"))
      (node (ref "X2") (pin "2") (pinfunction "2_2") (pintype "passive"))
    )
    (net (code "30") (name "/328P_AUTORESETn") (class "Default")
      (node (ref "C11") (pin "1") (pinfunction "1_1") (pintype "passive"))
      (node (ref "R18") (pin "1") (pinfunction "1_1") (pintype "passive"))
      (node (ref "U6") (pin "1") (pinfunction "1_1") (pintype "passive"))
    )
    (net (code "31") (name "/328P_BUF_RESETn") (class "Default")
      (node (ref "C32") (pin "2") (pinfunction "2_2") (pintype "passive"))
      (node (ref "R24") (pin "2") (pinfunction "2_2") (pintype "passive"))
      (node (ref "U6") (pin "2") (pinfunction "2_2") (pintype "passive"))
    )
    (net (code "32") (name "/328P_RESETn") (class "Default")
      (node (ref "J1") (pin "3") (pinfunction "3_3") (pintype "passive"))
      (node (ref "J5") (pin "5") (pinfunction "5_5") (pintype "passive"))
      (node (ref "JP3") (pin "1") (pinfunction "1_1") (pintype "passive"))
      (node (ref "R14") (pin "1") (pinfunction "1_1") (pintype "passive"))
      (node (ref "U3") (pin "1") (pinfunction "(PCINT14/RESET)_PC6_1") (pintype "passive"))
      (node (ref "U6") (pin "4") (pinfunction "4_4") (pintype "passive"))
    )
    (net (code "33") (name "/AD0") (class "Default")
      (node (ref "J2") (pin "1") (pinfunction "1_1") (pintype "passive"))
      (node (ref "U3") (pin "23") (pinfunction "PC0_(ADC0/PCINT8)_23") (pintype "passive"))
    )
    (net (code "34") (name "/AD1") (class "Default")
      (node (ref "J2") (pin "2") (pinfunction "2_2") (pintype "passive"))
      (node (ref "U3") (pin "24") (pinfunction "PC1_(ADC1/PCINT9)_24") (pintype "passive"))
    )
    (net (code "35") (name "/AD2") (class "Default")
      (node (ref "J2") (pin "3") (pinfunction "3_3") (pintype "passive"))
      (node (ref "U3") (pin "25") (pinfunction "PC2_(ADC2/PCINT10)_25") (pintype "passive"))
    )
    (net (code "36") (name "/AD3") (class "Default")
      (node (ref "J2") (pin "4") (pinfunction "4_4") (pintype "passive"))
      (node (ref "U3") (pin "26") (pinfunction "PC3_(ADC3/PCINT11)_26") (pintype "passive"))
    )
    (net (code "37") (name "/AD4{slash}SDA") (class "Default")
      (node (ref "J2") (pin "5") (pinfunction "5_5") (pintype "passive"))
      (node (ref "J4") (pin "9") (pinfunction "9_9") (pintype "passive"))
      (node (ref "U3") (pin "27") (pinfunction "PC4_(ADC4/SDA/PCINT12)_27") (pintype "passive"))
    )
    (net (code "38") (name "/AD5{slash}SCL") (class "Default")
      (node (ref "J2") (pin "6") (pinfunction "6_6") (pintype "passive"))
      (node (ref "J4") (pin "10") (pinfunction "10_10") (pintype "passive"))
      (node (ref "U3") (pin "28") (pinfunction "PC5_(ADC5/SCL/PCINT13)_28") (pintype "passive"))
    )
    (net (code "39") (name "/BUTTON_RESETn") (class "Default")
      (node (ref "D6") (pin "2") (pinfunction "Anode_2") (pintype "passive"))
      (node (ref "R20") (pin "1") (pinfunction "1_1") (pintype "passive"))
      (node (ref "R24") (pin "1") (pinfunction "1_1") (pintype "passive"))
      (node (ref "SW1") (pin "1") (pinfunction "1_1") (pintype "passive"))
      (node (ref "SW1") (pin "2") (pinfunction "2_2") (pintype "passive"))
    )
    (net (code "40") (name "/CONN_USB_N") (class "Default")
      (node (ref "J7") (pin "2") (pinfunction "2_2") (pintype "passive"))
      (node (ref "R6") (pin "1") (pinfunction "1_1") (pintype "passive"))
      (node (ref "Z1") (pin "2") (pinfunction "2_2") (pintype "passive"))
    )
    (net (code "41") (name "/CONN_USB_P") (class "Default")
      (node (ref "J7") (pin "3") (pinfunction "3_3") (pintype "passive"))
      (node (ref "R7") (pin "1") (pinfunction "1_1") (pintype "passive"))
      (node (ref "Z2") (pin "2") (pinfunction "2_2") (pintype "passive"))
    )
    (net (code "42") (name "/IO0{slash}RXD") (class "Default")
      (node (ref "J3") (pin "1") (pinfunction "1_1") (pintype "passive"))
      (node (ref "R10") (pin "2") (pinfunction "2_2") (pintype "passive"))
      (node (ref "U3") (pin "2") (pinfunction "(PCINT16/RXD)_PD0_2") (pintype "passive"))
    )
    (net (code "43") (name "/IO1{slash}TXD") (class "Default")
      (node (ref "J3") (pin "2") (pinfunction "2_2") (pintype "passive"))
      (node (ref "R11") (pin "2") (pinfunction "2_2") (pintype "passive"))
      (node (ref "U3") (pin "3") (pinfunction "(PCINT17/TXD)_PD1_3") (pintype "passive"))
    )
    (net (code "44") (name "/IO2") (class "Default")
      (node (ref "J3") (pin "3") (pinfunction "3_3") (pintype "passive"))
      (node (ref "U3") (pin "4") (pinfunction "(PCINT18/INT0)_PD2_4") (pintype "passive"))
    )
    (net (code "45") (name "/IO3") (class "Default")
      (node (ref "J3") (pin "4") (pinfunction "4_4") (pintype "passive"))
      (node (ref "U3") (pin "5") (pinfunction "(PCINT19/OC2B/INT1)_PD3_5") (pintype "passive"))
    )
    (net (code "46") (name "/IO4") (class "Default")
      (node (ref "J3") (pin "5") (pinfunction "5_5") (pintype "passive"))
      (node (ref "U3") (pin "6") (pinfunction "(PCINT20/XCK/T0)_PD4_6") (pintype "passive"))
    )
    (net (code "47") (name "/IO5") (class "Default")
      (node (ref "J3") (pin "6") (pinfunction "6_6") (pintype "passive"))
      (node (ref "U3") (pin "11") (pinfunction "(PCINT21/OC0B/T1)_PD5_11") (pintype "passive"))
    )
    (net (code "48") (name "/IO6") (class "Default")
      (node (ref "J3") (pin "7") (pinfunction "7_7") (pintype "passive"))
      (node (ref "U3") (pin "12") (pinfunction "(PCINT22/OC0A/AIN0)_PD6_12") (pintype "passive"))
    )
    (net (code "49") (name "/IO7") (class "Default")
      (node (ref "J3") (pin "8") (pinfunction "8_8") (pintype "passive"))
      (node (ref "U3") (pin "13") (pinfunction "(PCINT23/AIN1)_PD7_13") (pintype "passive"))
    )
    (net (code "50") (name "/IO8") (class "Default")
      (node (ref "J4") (pin "1") (pinfunction "1_1") (pintype "passive"))
      (node (ref "R22") (pin "2") (pinfunction "2_2") (pintype "passive"))
      (node (ref "U3") (pin "14") (pinfunction "(PCINT0/CLKO/ICP1)_PB0_14") (pintype "passive"))
    )
    (net (code "51") (name "/IO9") (class "Default")
      (node (ref "J4") (pin "2") (pinfunction "2_2") (pintype "passive"))
      (node (ref "U3") (pin "15") (pinfunction "PB1_(OC1A/PCINT1)_15") (pintype "passive"))
    )
    (net (code "52") (name "/MISO") (class "Default")
      (node (ref "J4") (pin "5") (pinfunction "5_5") (pintype "passive"))
      (node (ref "J5") (pin "1") (pinfunction "1_1") (pintype "passive"))
      (node (ref "U3") (pin "18") (pinfunction "PB4_(MISO/PCINT4)_18") (pintype "passive"))
    )
    (net (code "53") (name "/MOSI") (class "Default")
      (node (ref "J4") (pin "4") (pinfunction "4_4") (pintype "passive"))
      (node (ref "J5") (pin "4") (pinfunction "4_4") (pintype "passive"))
      (node (ref "U3") (pin "17") (pinfunction "PB3_(MOSI/OC2A/PCINT3)_17") (pintype "passive"))
    )
    (net (code "54") (name "/SCK") (class "Default")
      (node (ref "J4") (pin "6") (pinfunction "6_6") (pintype "passive"))
      (node (ref "J5") (pin "3") (pinfunction "3_3") (pintype "passive"))
      (node (ref "R13") (pin "2") (pinfunction "2_2") (pintype "passive"))
      (node (ref "U4") (pin "1") (pinfunction "1_1") (pintype "passive"))
      (node (ref "U4") (pin "2") (pinfunction "2_2") (pintype "passive"))
    )
    (net (code "55") (name "/SCK_R") (class "Default")
      (node (ref "R13") (pin "1") (pinfunction "1_1") (pintype "passive"))
      (node (ref "U3") (pin "19") (pinfunction "PB5_(SCK/PCINT5)_19") (pintype "passive"))
    )
    (net (code "56") (name "/SS") (class "Default")
      (node (ref "J4") (pin "3") (pinfunction "3_3") (pintype "passive"))
      (node (ref "U3") (pin "16") (pinfunction "PB2_(SS/OC1B/PCINT2)_16") (pintype "passive"))
    )
    (net (code "57") (name "/USB_N") (class "Default")
      (node (ref "R6") (pin "2") (pinfunction "2_2") (pintype "passive"))
      (node (ref "U1") (pin "30") (pinfunction "D-_30") (pintype "passive"))
    )
    (net (code "58") (name "/USB_P") (class "Default")
      (node (ref "R7") (pin "2") (pinfunction "2_2") (pintype "passive"))
      (node (ref "U1") (pin "29") (pinfunction "D+_29") (pintype "passive"))
    )
    (net (code "59") (name "/USER_BUTTON") (class "Default")
      (node (ref "R21") (pin "1") (pinfunction "1_1") (pintype "passive"))
      (node (ref "R25") (pin "1") (pinfunction "1_1") (pintype "passive"))
      (node (ref "SW2") (pin "1") (pinfunction "1_1") (pintype "passive"))
      (node (ref "SW2") (pin "2") (pinfunction "2_2") (pintype "passive"))
    )
    (net (code "60") (name "/USER_BUTTON_BUFFER") (class "Default")
      (node (ref "C33") (pin "2") (pinfunction "2_2") (pintype "passive"))
      (node (ref "R25") (pin "2") (pinfunction "2_2") (pintype "passive"))
      (node (ref "U7") (pin "1") (pinfunction "1_1") (pintype "passive"))
      (node (ref "U7") (pin "2") (pinfunction "2_2") (pintype "passive"))
    )
    (net (code "61") (name "GND") (class "Default")
      (node (ref "C1") (pin "2") (pinfunction "2_2") (pintype "passive"))
      (node (ref "C10") (pin "1") (pinfunction "1_1") (pintype "passive"))
      (node (ref "C12") (pin "1") (pinfunction "1_1") (pintype "passive"))
      (node (ref "C13") (pin "1") (pinfunction "1_1") (pintype "passive"))
      (node (ref "C14") (pin "1") (pinfunction "1_1") (pintype "passive"))
      (node (ref "C15") (pin "1") (pinfunction "1_1") (pintype "passive"))
      (node (ref "C16") (pin "1") (pinfunction "1_1") (pintype "passive"))
      (node (ref "C17") (pin "1") (pinfunction "1_1") (pintype "passive"))
      (node (ref "C19") (pin "1") (pinfunction "1_1") (pintype "passive"))
      (node (ref "C2") (pin "2") (pinfunction "2_2") (pintype "passive"))
      (node (ref "C20") (pin "1") (pinfunction "1_1") (pintype "passive"))
      (node (ref "C21") (pin "1") (pinfunction "1_1") (pintype "passive"))
      (node (ref "C22") (pin "1") (pinfunction "1_1") (pintype "passive"))
      (node (ref "C23") (pin "1") (pinfunction "1_1") (pintype "passive"))
      (node (ref "C24") (pin "1") (pinfunction "1_1") (pintype "passive"))
      (node (ref "C25") (pin "1") (pinfunction "1_1") (pintype "passive"))
      (node (ref "C26") (pin "1") (pinfunction "1_1") (pintype "passive"))
      (node (ref "C27") (pin "1") (pinfunction "1_1") (pintype "passive"))
      (node (ref "C28") (pin "1") (pinfunction "1_1") (pintype "passive"))
      (node (ref "C29") (pin "1") (pinfunction "1_1") (pintype "passive"))
      (node (ref "C3") (pin "1") (pinfunction "1_1") (pintype "passive"))
      (node (ref "C30") (pin "1") (pinfunction "1_1") (pintype "passive"))
      (node (ref "C31") (pin "1") (pinfunction "1_1") (pintype "passive"))
      (node (ref "C32") (pin "1") (pinfunction "1_1") (pintype "passive"))
      (node (ref "C33") (pin "1") (pinfunction "1_1") (pintype "passive"))
      (node (ref "C34") (pin "1") (pinfunction "1_1") (pintype "passive"))
      (node (ref "C4") (pin "1") (pinfunction "1_1") (pintype "passive"))
      (node (ref "C5") (pin "1") (pinfunction "1_1") (pintype "passive"))
      (node (ref "C6") (pin "1") (pinfunction "1_1") (pintype "passive"))
      (node (ref "C7") (pin "1") (pinfunction "1_1") (pintype "passive"))
      (node (ref "C8") (pin "1") (pinfunction "1_1") (pintype "passive"))
      (node (ref "C9") (pin "1") (pinfunction "1_1") (pintype "passive"))
      (node (ref "D1") (pin "1") (pinfunction "1_1") (pintype "passive"))
      (node (ref "J1") (pin "6") (pinfunction "6_6") (pintype "passive"))
      (node (ref "J1") (pin "7") (pinfunction "7_7") (pintype "passive"))
      (node (ref "J4") (pin "7") (pinfunction "7_7") (pintype "passive"))
      (node (ref "J5") (pin "6") (pinfunction "6_6") (pintype "passive"))
      (node (ref "J6") (pin "6") (pinfunction "6_6") (pintype "passive"))
      (node (ref "J7") (pin "10") (pinfunction "10_10") (pintype "passive"))
      (node (ref "J7") (pin "11") (pinfunction "11_11") (pintype "passive"))
      (node (ref "J7") (pin "5") (pinfunction "5_5") (pintype "passive"))
      (node (ref "J7") (pin "6") (pinfunction "6_6") (pintype "passive"))
      (node (ref "J7") (pin "7") (pinfunction "7_7") (pintype "passive"))
      (node (ref "J7") (pin "8") (pinfunction "8_8") (pintype "passive"))
      (node (ref "J7") (pin "9") (pinfunction "9_9") (pintype "passive"))
      (node (ref "J9") (pin "1") (pinfunction "1_1") (pintype "passive"))
      (node (ref "MH1") (pin "1") (pinfunction "1_1") (pintype "passive"))
      (node (ref "MH2") (pin "1") (pinfunction "1_1") (pintype "passive"))
      (node (ref "MH3") (pin "1") (pinfunction "1_1") (pintype "passive"))
      (node (ref "R12") (pin "1") (pinfunction "1_1") (pintype "passive"))
      (node (ref "R8") (pin "2") (pinfunction "2_2") (pintype "passive"))
      (node (ref "SW1") (pin "3") (pinfunction "3_3") (pintype "passive"))
      (node (ref "SW1") (pin "4") (pinfunction "4_4") (pintype "passive"))
      (node (ref "SW2") (pin "3") (pinfunction "3_3") (pintype "passive"))
      (node (ref "SW2") (pin "4") (pinfunction "4_4") (pintype "passive"))
      (node (ref "U1") (pin "28") (pinfunction "UGND_28") (pintype "passive"))
      (node (ref "U1") (pin "3") (pinfunction "GND_3") (pintype "passive"))
      (node (ref "U2") (pin "3") (pinfunction "GND_3") (pintype "passive"))
      (node (ref "U2") (pin "6") (pinfunction "EPAD_6") (pintype "passive"))
      (node (ref "U3") (pin "22") (pinfunction "GND_22") (pintype "passive"))
      (node (ref "U3") (pin "8") (pinfunction "GND_8") (pintype "passive"))
      (node (ref "U4") (pin "3") (pinfunction "3_3") (pintype "passive"))
      (node (ref "U5") (pin "3") (pinfunction "3_3") (pintype "passive"))
      (node (ref "U6") (pin "3") (pinfunction "3_3") (pintype "passive"))
      (node (ref "U7") (pin "3") (pinfunction "3_3") (pintype "passive"))
      (node (ref "Z1") (pin "1") (pinfunction "1_1") (pintype "passive"))
      (node (ref "Z2") (pin "1") (pinfunction "1_1") (pintype "passive"))
    )
    (net (code "62") (name "Net-(C11-Pad2)") (class "Default")
      (node (ref "C11") (pin "2") (pinfunction "2_2") (pintype "passive"))
      (node (ref "JP1") (pin "1") (pinfunction "1_1") (pintype "passive"))
    )
    (net (code "63") (name "Net-(D1-Pad2)") (class "Default")
      (node (ref "D1") (pin "2") (pinfunction "2_2") (pintype "passive"))
      (node (ref "R17") (pin "1") (pinfunction "1_1") (pintype "passive"))
    )
    (net (code "64") (name "Net-(D2-Pad1)") (class "Default")
      (node (ref "D2") (pin "1") (pinfunction "1_1") (pintype "passive"))
      (node (ref "U4") (pin "4") (pinfunction "4_4") (pintype "passive"))
    )
    (net (code "65") (name "Net-(D2-Pad2)") (class "Default")
      (node (ref "D2") (pin "2") (pinfunction "2_2") (pintype "passive"))
      (node (ref "R15") (pin "1") (pinfunction "1_1") (pintype "passive"))
    )
    (net (code "66") (name "Net-(D3-Pad2)") (class "Default")
      (node (ref "D3") (pin "2") (pinfunction "2_2") (pintype "passive"))
      (node (ref "R2") (pin "1") (pinfunction "1_1") (pintype "passive"))
    )
    (net (code "67") (name "Net-(D4-Pad2)") (class "Default")
      (node (ref "D4") (pin "2") (pinfunction "2_2") (pintype "passive"))
      (node (ref "R3") (pin "1") (pinfunction "1_1") (pintype "passive"))
    )
    (net (code "68") (name "Net-(D5-Anode)") (class "Default")
      (node (ref "D5") (pin "2") (pinfunction "Anode_2") (pintype "passive"))
      (node (ref "R19") (pin "1") (pinfunction "1_1") (pintype "passive"))
      (node (ref "R23") (pin "1") (pinfunction "1_1") (pintype "passive"))
    )
    (net (code "69") (name "Net-(J7-Pad4)") (class "Default")
      (node (ref "J7") (pin "4") (pinfunction "4_4") (pintype "passive"))
      (node (ref "R8") (pin "1") (pinfunction "1_1") (pintype "passive"))
    )
    (net (code "70") (name "Net-(JP1-Pad3)") (class "Default")
      (node (ref "JP1") (pin "3") (pinfunction "3_3") (pintype "passive"))
      (node (ref "R12") (pin "2") (pinfunction "2_2") (pintype "passive"))
    )
    (net (code "71") (name "Net-(R22-Pad1)") (class "Default")
      (node (ref "R22") (pin "1") (pinfunction "1_1") (pintype "passive"))
      (node (ref "U7") (pin "4") (pinfunction "4_4") (pintype "passive"))
    )
    (net (code "72") (name "unconnected-(J1-Pad1)") (class "Default")
      (node (ref "J1") (pin "1") (pinfunction "1_1") (pintype "passive+no_connect"))
    )
    (net (code "73") (name "unconnected-(J1-Pad8)") (class "Default")
      (node (ref "J1") (pin "8") (pinfunction "8_8") (pintype "passive+no_connect"))
    )
    (net (code "74") (name "unconnected-(MH4-Pad1)") (class "Default")
      (node (ref "MH4") (pin "1") (pinfunction "1_1") (pintype "passive+no_connect"))
    )
    (net (code "75") (name "unconnected-(U1-(AIN0_{slash}_INT1)_PD1-Pad7)") (class "Default")
      (node (ref "U1") (pin "7") (pinfunction "(AIN0_/_INT1)_PD1_7") (pintype "passive+no_connect"))
    )
    (net (code "76") (name "unconnected-(U1-(OC.0B_{slash}_INT0)_PD0-Pad6)") (class "Default")
      (node (ref "U1") (pin "6") (pinfunction "(OC.0B_/_INT0)_PD0_6") (pintype "passive+no_connect"))
    )
    (net (code "77") (name "unconnected-(U1-(PCINT11_{slash}AIN2_)_PC2-Pad5)") (class "Default")
      (node (ref "U1") (pin "5") (pinfunction "(PCINT11_/AIN2_)_PC2_5") (pintype "passive+no_connect"))
    )
    (net (code "78") (name "unconnected-(U1-(RTS_{slash}_AIN5_{slash}_INT6)_PD6-Pad12)") (class "Default")
      (node (ref "U1") (pin "12") (pinfunction "(RTS_/_AIN5_/_INT6)_PD6_12") (pintype "passive+no_connect"))
    )
    (net (code "79") (name "unconnected-(U1-(SS_{slash}_PCINT0)_PB0-Pad14)") (class "Default")
      (node (ref "U1") (pin "14") (pinfunction "(SS_/_PCINT0)_PB0_14") (pintype "passive+no_connect"))
    )
    (net (code "80") (name "unconnected-(U1-PC4_(PCINT10)-Pad26)") (class "Default")
      (node (ref "U1") (pin "26") (pinfunction "PC4_(PCINT10)_26") (pintype "passive+no_connect"))
    )
    (net (code "81") (name "unconnected-(U1-PC5_(_PCINT9{slash}_OC.1B)-Pad25)") (class "Default")
      (node (ref "U1") (pin "25") (pinfunction "PC5_(_PCINT9/_OC.1B)_25") (pintype "passive+no_connect"))
    )
    (net (code "82") (name "unconnected-(U1-PC6_(OC.1A_{slash}_PCINT8)-Pad23)") (class "Default")
      (node (ref "U1") (pin "23") (pinfunction "PC6_(OC.1A_/_PCINT8)_23") (pintype "passive+no_connect"))
    )
    (net (code "83") (name "unconnected-(U1-PC7_(INT4_{slash}_ICP1_{slash}_CLKO)-Pad22)") (class "Default")
      (node (ref "U1") (pin "22") (pinfunction "PC7_(INT4_/_ICP1_/_CLKO)_22") (pintype "passive+no_connect"))
    )
  )
)
